# Modular-LED-Lamp_driver_integrated.net
KiCad netlist of a schematic drawn in EAGLE
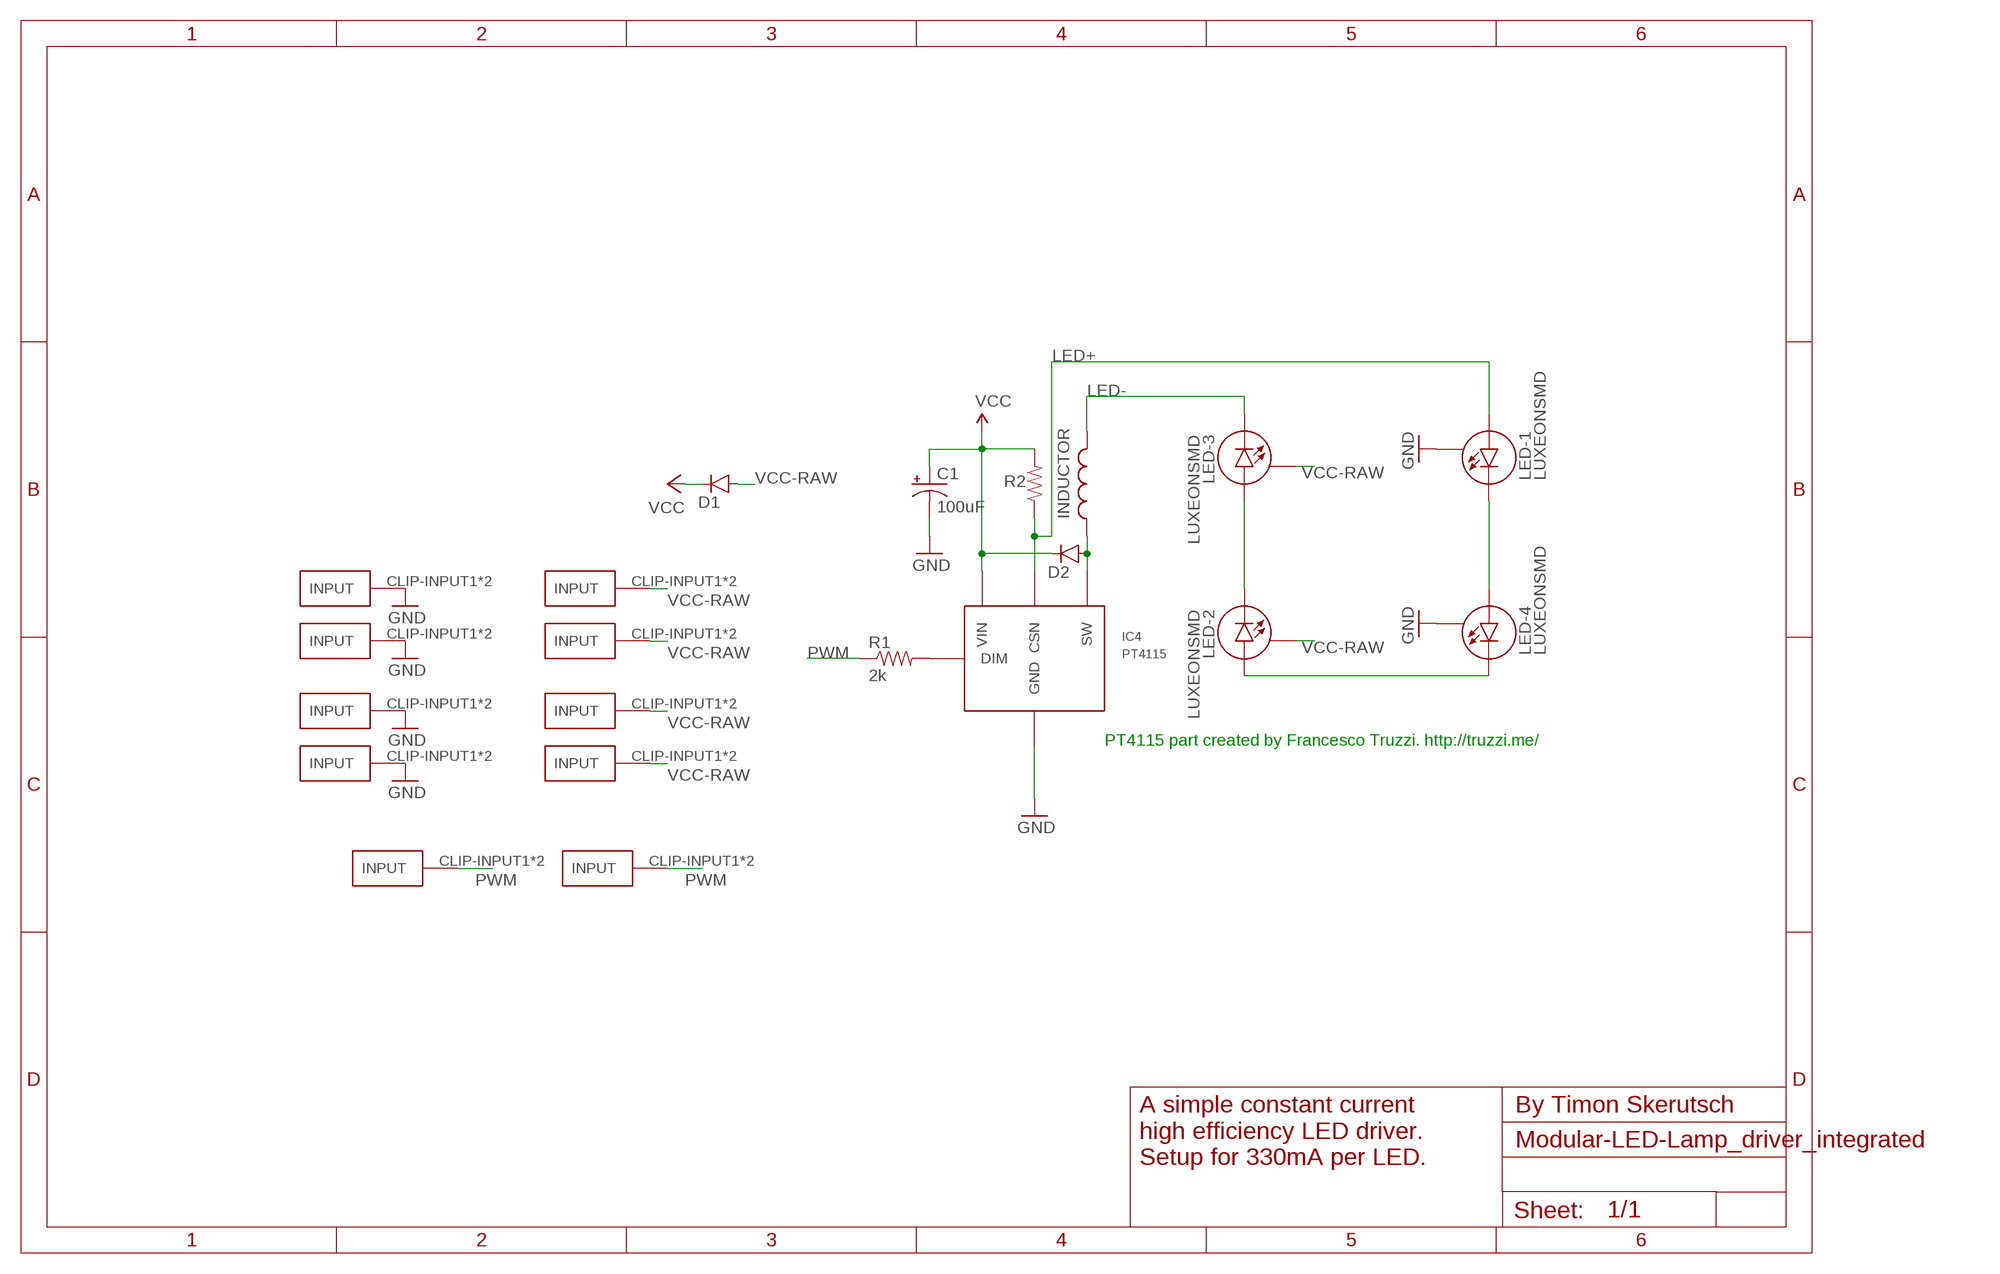
[diagram p0: schematic, sheet 1]

(export (version "E")
  (design (tool "Eeschema 10.0.6"))
  (components
    (comp (ref "C1")
      (value "100uF")
      (footprint "eagle-import:PANASONIC_E")
      (libsource (lib "eagle-import") (part "CAP_POLE"))
    )
    (comp (ref "D1")
      (value "DIODESMA-KIT")
      (footprint "eagle-import:SMA-DIODE-KIT")
      (libsource (lib "eagle-import") (part "DIODESMA-KIT"))
    )
    (comp (ref "D2")
      (value "DIODESMA-KIT")
      (footprint "eagle-import:SMA-DIODE-KIT")
      (libsource (lib "eagle-import") (part "DIODESMA-KIT"))
    )
    (comp (ref "GND-CLIP")
      (value "FUSE-HOLDER-5X20MM")
      (footprint "eagle-import:FUSE-HOLDER-5X20MM")
      (libsource (lib "eagle-import") (part "FUSE-HOLDER-5X20MM"))
    )
    (comp (ref "GND-CLIP1")
      (value "FUSE-HOLDER-5X20MM")
      (footprint "eagle-import:FUSE-HOLDER-5X20MM")
      (libsource (lib "eagle-import") (part "FUSE-HOLDER-5X20MM"))
    )
    (comp (ref "GND-CLIP2")
      (value "FUSE-HOLDER-5X20MM")
      (footprint "eagle-import:FUSE-HOLDER-5X20MM")
      (libsource (lib "eagle-import") (part "FUSE-HOLDER-5X20MM"))
    )
    (comp (ref "GND-CLIP3")
      (value "FUSE-HOLDER-5X20MM")
      (footprint "eagle-import:FUSE-HOLDER-5X20MM")
      (libsource (lib "eagle-import") (part "FUSE-HOLDER-5X20MM"))
    )
    (comp (ref "IC4")
      (value "PT4115")
      (footprint "eagle-import:PT4115")
      (libsource (lib "eagle-import") (part "PT4115"))
    )
    (comp (ref "INDUCTOR")
      (value "MSS1260")
      (footprint "eagle-import:MSS1260")
      (libsource (lib "eagle-import") (part "MSS1260"))
    )
    (comp (ref "LED-1")
      (value "LUXEONSMD")
      (footprint "eagle-import:LUXEON")
      (libsource (lib "eagle-import") (part "LUXEONSMD"))
    )
    (comp (ref "LED-2")
      (value "LUXEONSMD")
      (footprint "eagle-import:LUXEON")
      (libsource (lib "eagle-import") (part "LUXEONSMD"))
    )
    (comp (ref "LED-3")
      (value "LUXEONSMD")
      (footprint "eagle-import:LUXEON")
      (libsource (lib "eagle-import") (part "LUXEONSMD"))
    )
    (comp (ref "LED-4")
      (value "LUXEONSMD")
      (footprint "eagle-import:LUXEON")
      (libsource (lib "eagle-import") (part "LUXEONSMD"))
    )
    (comp (ref "PWM-CLIP")
      (value "FUSE-HOLDER-5X20MM")
      (footprint "eagle-import:FUSE-HOLDER-5X20MM")
      (libsource (lib "eagle-import") (part "FUSE-HOLDER-5X20MM"))
    )
    (comp (ref "PWM-CLIP1")
      (value "FUSE-HOLDER-5X20MM")
      (footprint "eagle-import:FUSE-HOLDER-5X20MM")
      (libsource (lib "eagle-import") (part "FUSE-HOLDER-5X20MM"))
    )
    (comp (ref "R1")
      (value "2k")
      (footprint "eagle-import:1206")
      (libsource (lib "eagle-import") (part "RESISTOR1206"))
    )
    (comp (ref "R2")
      (value "0.3")
      (footprint "eagle-import:1206")
      (libsource (lib "eagle-import") (part "RESISTOR1206"))
    )
    (comp (ref "VCC-CLIP")
      (value "FUSE-HOLDER-5X20MM")
      (footprint "eagle-import:FUSE-HOLDER-5X20MM")
      (libsource (lib "eagle-import") (part "FUSE-HOLDER-5X20MM"))
    )
    (comp (ref "VCC-CLIP1")
      (value "FUSE-HOLDER-5X20MM")
      (footprint "eagle-import:FUSE-HOLDER-5X20MM")
      (libsource (lib "eagle-import") (part "FUSE-HOLDER-5X20MM"))
    )
    (comp (ref "VCC-CLIP2")
      (value "FUSE-HOLDER-5X20MM")
      (footprint "eagle-import:FUSE-HOLDER-5X20MM")
      (libsource (lib "eagle-import") (part "FUSE-HOLDER-5X20MM"))
    )
    (comp (ref "VCC-CLIP3")
      (value "FUSE-HOLDER-5X20MM")
      (footprint "eagle-import:FUSE-HOLDER-5X20MM")
      (libsource (lib "eagle-import") (part "FUSE-HOLDER-5X20MM"))
    )
  )
  (nets
    (net (code "1") (name "/LED+") (class "Default")
      (node (ref "IC4") (pin "4") (pinfunction "CSN_4") (pintype "bidirectional"))
      (node (ref "LED-1") (pin "A") (pinfunction "A_A") (pintype "passive"))
      (node (ref "R2") (pin "1") (pinfunction "1_1") (pintype "passive"))
    )
    (net (code "2") (name "/LED-") (class "Default")
      (node (ref "INDUCTOR") (pin "P$1") (pinfunction "P$1_P$1") (pintype "passive"))
      (node (ref "LED-3") (pin "C") (pinfunction "C_C") (pintype "passive"))
    )
    (net (code "3") (name "/PWM") (class "Default")
      (node (ref "PWM-CLIP") (pin "CLIP-INPUT1") (pinfunction "INPUT_CLIP-INPUT1") (pintype "bidirectional"))
      (node (ref "PWM-CLIP") (pin "CLIP-INPUT2") (pinfunction "INPUT_CLIP-INPUT2") (pintype "bidirectional"))
      (node (ref "PWM-CLIP1") (pin "CLIP-INPUT1") (pinfunction "INPUT_CLIP-INPUT1") (pintype "bidirectional"))
      (node (ref "PWM-CLIP1") (pin "CLIP-INPUT2") (pinfunction "INPUT_CLIP-INPUT2") (pintype "bidirectional"))
      (node (ref "R1") (pin "1") (pinfunction "1_1") (pintype "passive"))
    )
    (net (code "4") (name "/VCC-RAW") (class "Default")
      (node (ref "D1") (pin "A") (pinfunction "A_A") (pintype "passive"))
      (node (ref "LED-2") (pin "S") (pinfunction "S_S") (pintype "bidirectional"))
      (node (ref "LED-3") (pin "S") (pinfunction "S_S") (pintype "bidirectional"))
      (node (ref "VCC-CLIP") (pin "CLIP-INPUT1") (pinfunction "INPUT_CLIP-INPUT1") (pintype "bidirectional"))
      (node (ref "VCC-CLIP") (pin "CLIP-INPUT2") (pinfunction "INPUT_CLIP-INPUT2") (pintype "bidirectional"))
      (node (ref "VCC-CLIP1") (pin "CLIP-INPUT1") (pinfunction "INPUT_CLIP-INPUT1") (pintype "bidirectional"))
      (node (ref "VCC-CLIP1") (pin "CLIP-INPUT2") (pinfunction "INPUT_CLIP-INPUT2") (pintype "bidirectional"))
      (node (ref "VCC-CLIP2") (pin "CLIP-INPUT1") (pinfunction "INPUT_CLIP-INPUT1") (pintype "bidirectional"))
      (node (ref "VCC-CLIP2") (pin "CLIP-INPUT2") (pinfunction "INPUT_CLIP-INPUT2") (pintype "bidirectional"))
      (node (ref "VCC-CLIP3") (pin "CLIP-INPUT1") (pinfunction "INPUT_CLIP-INPUT1") (pintype "bidirectional"))
      (node (ref "VCC-CLIP3") (pin "CLIP-INPUT2") (pinfunction "INPUT_CLIP-INPUT2") (pintype "bidirectional"))
    )
    (net (code "5") (name "GND") (class "Default")
      (node (ref "C1") (pin "-") (pinfunction "-_-") (pintype "passive"))
      (node (ref "GND-CLIP") (pin "CLIP-INPUT1") (pinfunction "INPUT_CLIP-INPUT1") (pintype "bidirectional"))
      (node (ref "GND-CLIP") (pin "CLIP-INPUT2") (pinfunction "INPUT_CLIP-INPUT2") (pintype "bidirectional"))
      (node (ref "GND-CLIP1") (pin "CLIP-INPUT1") (pinfunction "INPUT_CLIP-INPUT1") (pintype "bidirectional"))
      (node (ref "GND-CLIP1") (pin "CLIP-INPUT2") (pinfunction "INPUT_CLIP-INPUT2") (pintype "bidirectional"))
      (node (ref "GND-CLIP2") (pin "CLIP-INPUT1") (pinfunction "INPUT_CLIP-INPUT1") (pintype "bidirectional"))
      (node (ref "GND-CLIP2") (pin "CLIP-INPUT2") (pinfunction "INPUT_CLIP-INPUT2") (pintype "bidirectional"))
      (node (ref "GND-CLIP3") (pin "CLIP-INPUT1") (pinfunction "INPUT_CLIP-INPUT1") (pintype "bidirectional"))
      (node (ref "GND-CLIP3") (pin "CLIP-INPUT2") (pinfunction "INPUT_CLIP-INPUT2") (pintype "bidirectional"))
      (node (ref "IC4") (pin "2") (pinfunction "GND_2") (pintype "power_in"))
      (node (ref "IC4") (pin "2A") (pinfunction "GND_2A") (pintype "power_in"))
      (node (ref "LED-1") (pin "S") (pinfunction "S_S") (pintype "bidirectional"))
      (node (ref "LED-4") (pin "S") (pinfunction "S_S") (pintype "bidirectional"))
    )
    (net (code "6") (name "Net-(IC4-DIM)") (class "Default")
      (node (ref "IC4") (pin "3") (pinfunction "DIM_3") (pintype "bidirectional"))
      (node (ref "R1") (pin "2") (pinfunction "2_2") (pintype "passive"))
    )
    (net (code "7") (name "Net-(IC4-SW)") (class "Default")
      (node (ref "D2") (pin "A") (pinfunction "A_A") (pintype "passive"))
      (node (ref "IC4") (pin "1") (pinfunction "SW_1") (pintype "bidirectional"))
      (node (ref "INDUCTOR") (pin "P$2") (pinfunction "P$2_P$2") (pintype "passive"))
    )
    (net (code "8") (name "Net-(LED-1-PadC)") (class "Default")
      (node (ref "LED-1") (pin "C") (pinfunction "C_C") (pintype "passive"))
      (node (ref "LED-4") (pin "A") (pinfunction "A_A") (pintype "passive"))
    )
    (net (code "9") (name "Net-(LED-2-PadA)") (class "Default")
      (node (ref "LED-2") (pin "A") (pinfunction "A_A") (pintype "passive"))
      (node (ref "LED-4") (pin "C") (pinfunction "C_C") (pintype "passive"))
    )
    (net (code "10") (name "Net-(LED-2-PadC)") (class "Default")
      (node (ref "LED-2") (pin "C") (pinfunction "C_C") (pintype "passive"))
      (node (ref "LED-3") (pin "A") (pinfunction "A_A") (pintype "passive"))
    )
    (net (code "11") (name "VCC") (class "Default")
      (node (ref "C1") (pin "+") (pinfunction "+_+") (pintype "passive"))
      (node (ref "D1") (pin "C") (pinfunction "C_C") (pintype "passive"))
      (node (ref "D2") (pin "C") (pinfunction "C_C") (pintype "passive"))
      (node (ref "IC4") (pin "5") (pinfunction "VIN_5") (pintype "bidirectional"))
      (node (ref "R2") (pin "2") (pinfunction "2_2") (pintype "passive"))
    )
  )
)
